# VGA.net
KiCad netlist of a schematic drawn in Altium Designer
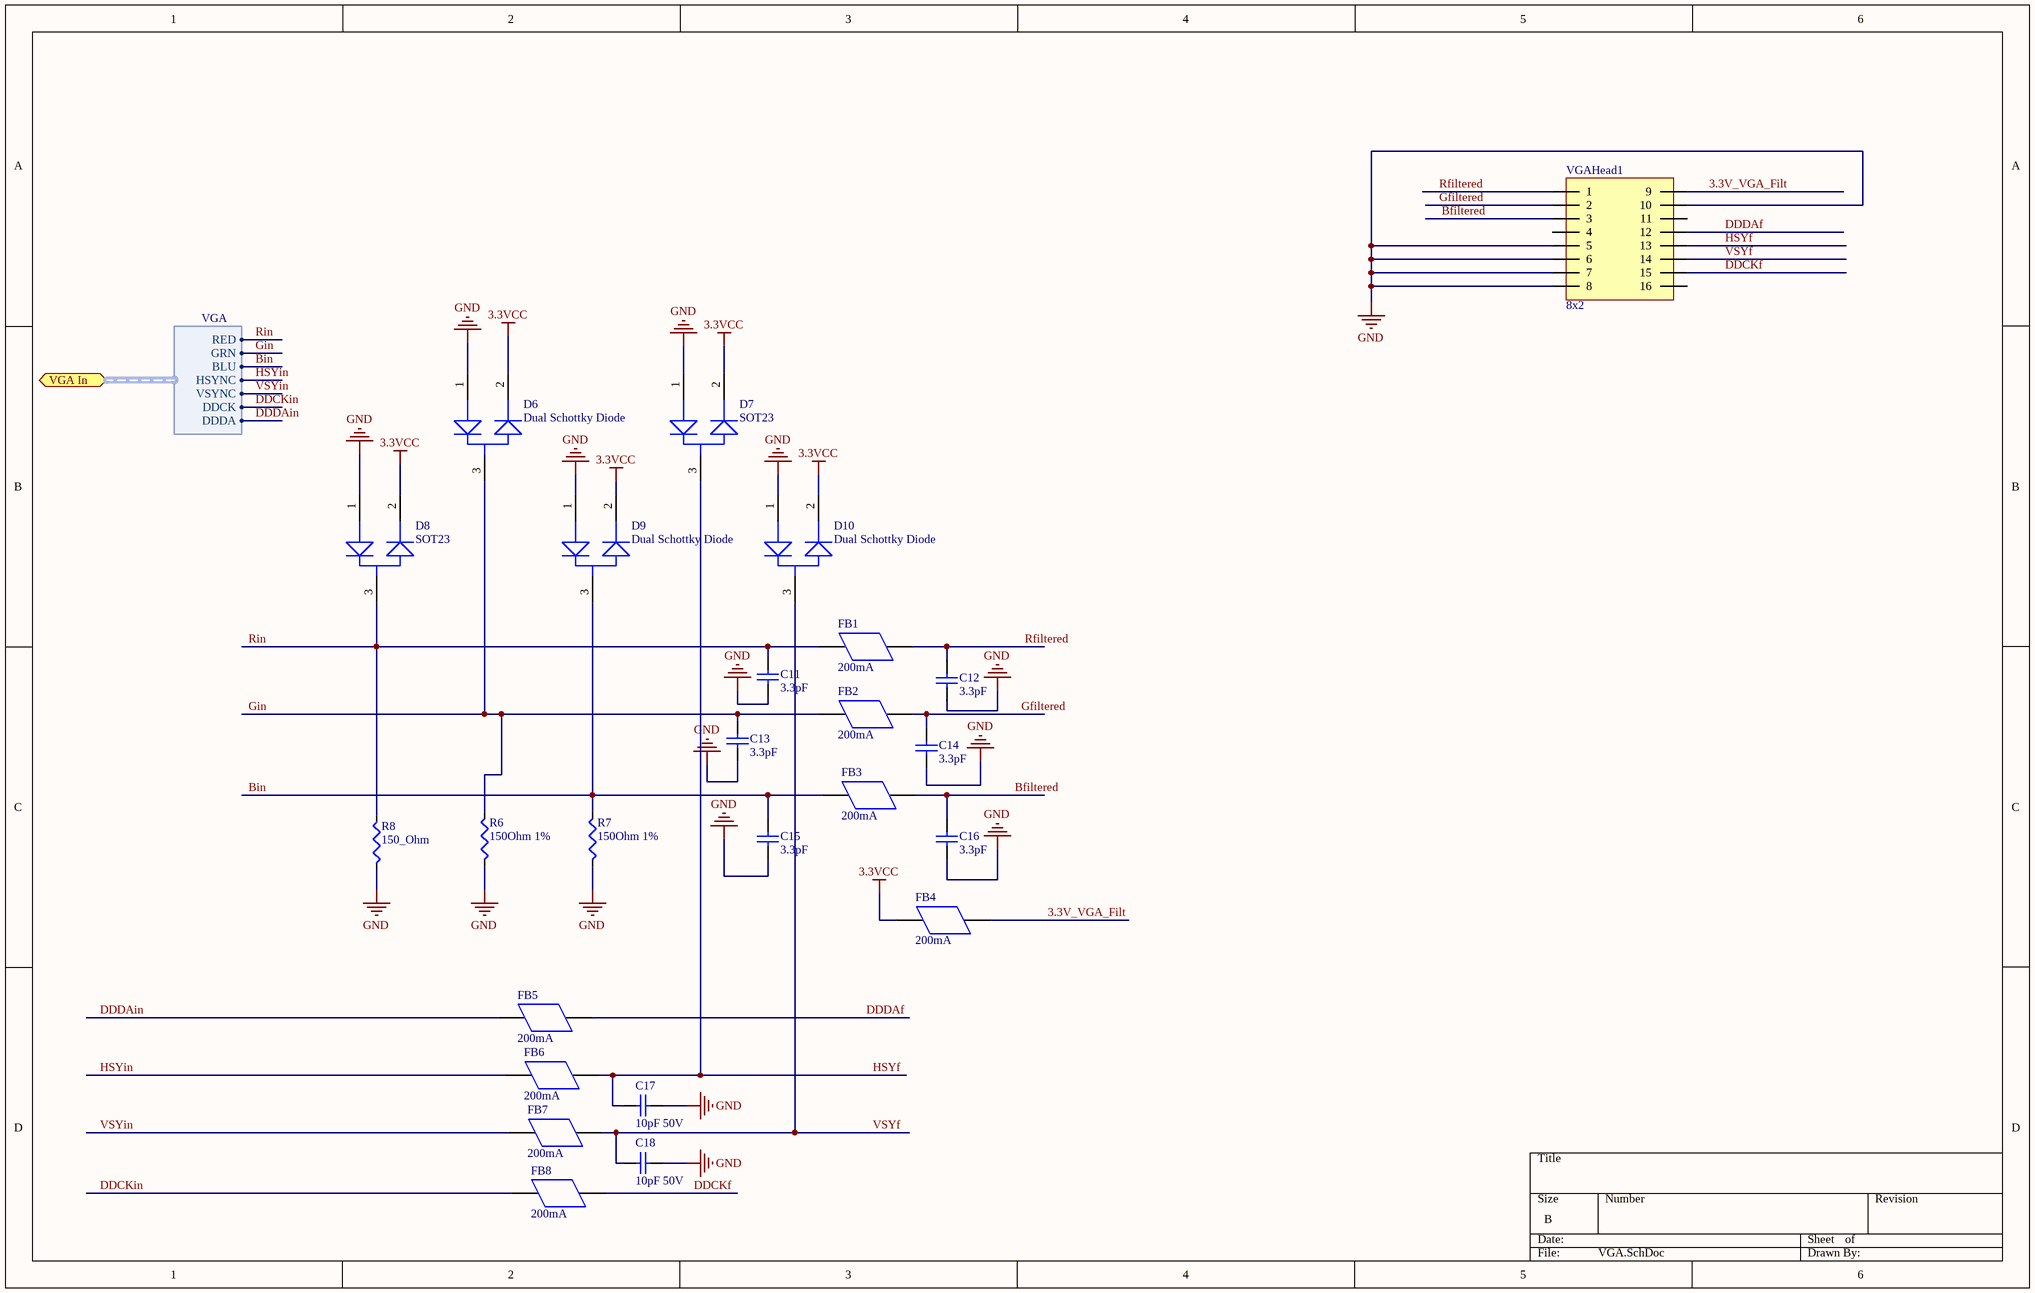
[diagram p0: VGA.SchDoc]

(export (version "E")
  (design (tool "Eeschema 10.0.6"))
  (components
    (comp (ref "C11")
      (value "3.3pF")
      (footprint "0805 (2012) Capacitor")
      (description "Capacitor")
      (libsource (lib "PassiveComponents") (part "Capacitor (non-polarized)"))
    )
    (comp (ref "C12")
      (value "3.3pF")
      (footprint "0805 (2012) Capacitor")
      (description "Capacitor")
      (libsource (lib "PassiveComponents") (part "Capacitor (non-polarized)"))
    )
    (comp (ref "C13")
      (value "3.3pF")
      (footprint "0805 (2012) Capacitor")
      (description "Capacitor")
      (libsource (lib "PassiveComponents") (part "Capacitor (non-polarized)"))
    )
    (comp (ref "C14")
      (value "3.3pF")
      (footprint "PassiveComponents:0805 (2012) Capacitor")
      (description "Capacitor")
      (libsource (lib "PassiveComponents") (part "Capacitor (non-polarized)"))
    )
    (comp (ref "C15")
      (value "3.3pF")
      (footprint "PassiveComponents:0805 (2012) Capacitor")
      (description "Capacitor")
      (libsource (lib "PassiveComponents") (part "Capacitor (non-polarized)"))
    )
    (comp (ref "C16")
      (value "3.3pF")
      (footprint "0805 (2012) Capacitor")
      (description "Capacitor")
      (libsource (lib "PassiveComponents") (part "Capacitor (non-polarized)"))
    )
    (comp (ref "C17")
      (value "10pF 50V")
      (footprint "PassiveComponents:0805 (2012) Capacitor")
      (description "Capacitor")
      (libsource (lib "PassiveComponents") (part "Capacitor (non-polarized)"))
    )
    (comp (ref "C18")
      (value "10pF 50V")
      (footprint "PassiveComponents:0805 (2012) Capacitor")
      (description "Capacitor")
      (libsource (lib "PassiveComponents") (part "Capacitor (non-polarized)"))
    )
    (comp (ref "D6")
      (value "Dual Schottky Diode")
      (footprint "SOT23")
      (libsource (lib "PassiveComponents") (part "Dual Schottky Diode"))
    )
    (comp (ref "D7")
      (value "SOT23")
      (footprint "SOT23")
      (description "Dual Schottky Diode")
      (libsource (lib "PassiveComponents") (part "Dual Schottky Diode"))
    )
    (comp (ref "D8")
      (value "SOT23")
      (footprint "SOT23")
      (description "Dual Schottky Diode")
      (libsource (lib "PassiveComponents") (part "Dual Schottky Diode"))
    )
    (comp (ref "D9")
      (value "Dual Schottky Diode")
      (footprint "PassiveComponents:SOT23")
      (libsource (lib "PassiveComponents") (part "Dual Schottky Diode"))
    )
    (comp (ref "D10")
      (value "Dual Schottky Diode")
      (footprint "SOT23")
      (libsource (lib "PassiveComponents") (part "Dual Schottky Diode"))
    )
    (comp (ref "FB1")
      (value "200mA")
      (footprint "0805 (2012) Capacitor")
      (description "Ferrite Beads")
      (libsource (lib "PassiveComponents") (part "Ferrite Beads"))
    )
    (comp (ref "FB2")
      (value "200mA")
      (footprint "0805 (2012) Capacitor")
      (description "Ferrite Beads")
      (libsource (lib "PassiveComponents") (part "Ferrite Beads"))
    )
    (comp (ref "FB3")
      (value "200mA")
      (footprint "0805 (2012) Capacitor")
      (description "Ferrite Beads")
      (libsource (lib "PassiveComponents") (part "Ferrite Beads"))
    )
    (comp (ref "FB4")
      (value "200mA")
      (footprint "0805 (2012) Capacitor")
      (description "Ferrite Beads")
      (libsource (lib "PassiveComponents") (part "Ferrite Beads"))
    )
    (comp (ref "FB5")
      (value "200mA")
      (footprint "0805 (2012) Capacitor")
      (description "Ferrite Beads")
      (libsource (lib "PassiveComponents") (part "Ferrite Beads"))
    )
    (comp (ref "FB6")
      (value "200mA")
      (footprint "PassiveComponents:0805 (2012) Capacitor")
      (description "Ferrite Beads")
      (libsource (lib "PassiveComponents") (part "Ferrite Beads"))
    )
    (comp (ref "FB7")
      (value "200mA")
      (footprint "PassiveComponents:0805 (2012) Capacitor")
      (description "Ferrite Beads")
      (libsource (lib "PassiveComponents") (part "Ferrite Beads"))
    )
    (comp (ref "FB8")
      (value "200mA")
      (footprint "PassiveComponents:0805 (2012) Capacitor")
      (description "Ferrite Beads")
      (libsource (lib "PassiveComponents") (part "Ferrite Beads"))
    )
    (comp (ref "R6")
      (value "150Ohm 1%")
      (footprint "R 0805 (2012) RESISTOR")
      (description "Resistor")
      (libsource (lib "PassiveComponents") (part "Resistor"))
    )
    (comp (ref "R7")
      (value "150Ohm 1%")
      (footprint "R 0805 (2012) RESISTOR")
      (description "Resistor")
      (libsource (lib "PassiveComponents") (part "Resistor"))
    )
    (comp (ref "R8")
      (value "150_Ohm")
      (footprint "R 0805 (2012) RESISTOR")
      (description "Resistor")
      (libsource (lib "PassiveComponents") (part "Resistor"))
    )
    (comp (ref "VGAHead1")
      (value "8x2")
      (footprint "Headers:Male 8x2")
      (description "8x2 100mil Header")
      (libsource (lib "Headers") (part "8x2"))
    )
  )
  (nets
    (net (code "2") (name "/3.3V_VGA_Filt") (class "Default")
      (node (ref "FB4") (pin "2") (pinfunction "2_2") (pintype "passive"))
      (node (ref "VGAHead1") (pin "9") (pinfunction "9_9") (pintype "passive"))
    )
    (net (code "3") (name "/Bfiltered") (class "Default")
      (node (ref "C16") (pin "1") (pinfunction "1_1") (pintype "passive"))
      (node (ref "FB3") (pin "2") (pinfunction "2_2") (pintype "passive"))
      (node (ref "VGAHead1") (pin "3") (pinfunction "3_3") (pintype "passive"))
    )
    (net (code "4") (name "/Bin") (class "Default")
      (node (ref "C15") (pin "1") (pinfunction "1_1") (pintype "passive"))
      (node (ref "D9") (pin "3") (pinfunction "3_3") (pintype "passive"))
      (node (ref "FB3") (pin "1") (pinfunction "1_1") (pintype "passive"))
      (node (ref "R7") (pin "2") (pinfunction "2_2") (pintype "passive"))
    )
    (net (code "5") (name "/DDCKf") (class "Default")
      (node (ref "FB8") (pin "2") (pinfunction "2_2") (pintype "passive"))
      (node (ref "VGAHead1") (pin "15") (pinfunction "15_15") (pintype "passive"))
    )
    (net (code "6") (name "/DDCKin") (class "Default")
      (node (ref "FB8") (pin "1") (pinfunction "1_1") (pintype "passive"))
    )
    (net (code "7") (name "/DDDAf") (class "Default")
      (node (ref "FB5") (pin "2") (pinfunction "2_2") (pintype "passive"))
      (node (ref "VGAHead1") (pin "12") (pinfunction "12_12") (pintype "passive"))
    )
    (net (code "8") (name "/DDDAin") (class "Default")
      (node (ref "FB5") (pin "1") (pinfunction "1_1") (pintype "passive"))
    )
    (net (code "9") (name "/Gfiltered") (class "Default")
      (node (ref "C14") (pin "1") (pinfunction "1_1") (pintype "passive"))
      (node (ref "FB2") (pin "2") (pinfunction "2_2") (pintype "passive"))
      (node (ref "VGAHead1") (pin "2") (pinfunction "2_2") (pintype "passive"))
    )
    (net (code "10") (name "/Gin") (class "Default")
      (node (ref "C13") (pin "1") (pinfunction "1_1") (pintype "passive"))
      (node (ref "D6") (pin "3") (pinfunction "3_3") (pintype "passive"))
      (node (ref "FB2") (pin "1") (pinfunction "1_1") (pintype "passive"))
      (node (ref "R6") (pin "2") (pinfunction "2_2") (pintype "passive"))
    )
    (net (code "11") (name "/HSYf") (class "Default")
      (node (ref "C17") (pin "2") (pinfunction "2_2") (pintype "passive"))
      (node (ref "D7") (pin "3") (pinfunction "3_3") (pintype "passive"))
      (node (ref "FB6") (pin "2") (pinfunction "2_2") (pintype "passive"))
      (node (ref "VGAHead1") (pin "13") (pinfunction "13_13") (pintype "passive"))
    )
    (net (code "12") (name "/HSYin") (class "Default")
      (node (ref "FB6") (pin "1") (pinfunction "1_1") (pintype "passive"))
    )
    (net (code "13") (name "/Rfiltered") (class "Default")
      (node (ref "C12") (pin "1") (pinfunction "1_1") (pintype "passive"))
      (node (ref "FB1") (pin "2") (pinfunction "2_2") (pintype "passive"))
      (node (ref "VGAHead1") (pin "1") (pinfunction "1_1") (pintype "passive"))
    )
    (net (code "14") (name "/Rin") (class "Default")
      (node (ref "C11") (pin "1") (pinfunction "1_1") (pintype "passive"))
      (node (ref "D8") (pin "3") (pinfunction "3_3") (pintype "passive"))
      (node (ref "FB1") (pin "1") (pinfunction "1_1") (pintype "passive"))
      (node (ref "R8") (pin "2") (pinfunction "2_2") (pintype "passive"))
    )
    (net (code "15") (name "/VSYf") (class "Default")
      (node (ref "C18") (pin "2") (pinfunction "2_2") (pintype "passive"))
      (node (ref "D10") (pin "3") (pinfunction "3_3") (pintype "passive"))
      (node (ref "FB7") (pin "2") (pinfunction "2_2") (pintype "passive"))
      (node (ref "VGAHead1") (pin "14") (pinfunction "14_14") (pintype "passive"))
    )
    (net (code "16") (name "/VSYin") (class "Default")
      (node (ref "FB7") (pin "1") (pinfunction "1_1") (pintype "passive"))
    )
    (net (code "18") (name "3.3VCC") (class "Default")
      (node (ref "D10") (pin "2") (pinfunction "2_2") (pintype "passive"))
      (node (ref "D6") (pin "2") (pinfunction "2_2") (pintype "passive"))
      (node (ref "D7") (pin "2") (pinfunction "2_2") (pintype "passive"))
      (node (ref "D8") (pin "2") (pinfunction "2_2") (pintype "passive"))
      (node (ref "D9") (pin "2") (pinfunction "2_2") (pintype "passive"))
      (node (ref "FB4") (pin "1") (pinfunction "1_1") (pintype "passive"))
    )
    (net (code "19") (name "GND") (class "Default")
      (node (ref "C11") (pin "2") (pinfunction "2_2") (pintype "passive"))
      (node (ref "C12") (pin "2") (pinfunction "2_2") (pintype "passive"))
      (node (ref "C13") (pin "2") (pinfunction "2_2") (pintype "passive"))
      (node (ref "C14") (pin "2") (pinfunction "2_2") (pintype "passive"))
      (node (ref "C15") (pin "2") (pinfunction "2_2") (pintype "passive"))
      (node (ref "C16") (pin "2") (pinfunction "2_2") (pintype "passive"))
      (node (ref "C17") (pin "1") (pinfunction "1_1") (pintype "passive"))
      (node (ref "C18") (pin "1") (pinfunction "1_1") (pintype "passive"))
      (node (ref "D10") (pin "1") (pinfunction "1_1") (pintype "passive"))
      (node (ref "D6") (pin "1") (pinfunction "1_1") (pintype "passive"))
      (node (ref "D7") (pin "1") (pinfunction "1_1") (pintype "passive"))
      (node (ref "D8") (pin "1") (pinfunction "1_1") (pintype "passive"))
      (node (ref "D9") (pin "1") (pinfunction "1_1") (pintype "passive"))
      (node (ref "R6") (pin "1") (pinfunction "1_1") (pintype "passive"))
      (node (ref "R7") (pin "1") (pinfunction "1_1") (pintype "passive"))
      (node (ref "R8") (pin "1") (pinfunction "1_1") (pintype "passive"))
      (node (ref "VGAHead1") (pin "10") (pinfunction "10_10") (pintype "passive"))
      (node (ref "VGAHead1") (pin "5") (pinfunction "5_5") (pintype "passive"))
      (node (ref "VGAHead1") (pin "6") (pinfunction "6_6") (pintype "passive"))
      (node (ref "VGAHead1") (pin "7") (pinfunction "7_7") (pintype "passive"))
      (node (ref "VGAHead1") (pin "8") (pinfunction "8_8") (pintype "passive"))
    )
    (net (code "20") (name "unconnected-(VGAHead1-Pad4)") (class "Default")
      (node (ref "VGAHead1") (pin "4") (pinfunction "4_4") (pintype "passive"))
    )
    (net (code "21") (name "unconnected-(VGAHead1-Pad11)") (class "Default")
      (node (ref "VGAHead1") (pin "11") (pinfunction "11_11") (pintype "passive"))
    )
    (net (code "22") (name "unconnected-(VGAHead1-Pad16)") (class "Default")
      (node (ref "VGAHead1") (pin "16") (pinfunction "16_16") (pintype "passive"))
    )
  )
)
